# question_1.net
KiCad netlist of a schematic drawn in EAGLE
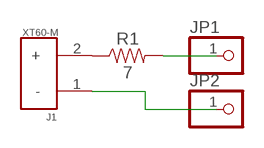
[diagram p0: schematic, sheet 1]

(export (version "E")
  (design (tool "Eeschema 10.0.6"))
  (components
    (comp (ref "J1")
      (value "XT60-M")
      (footprint "eagle-import:AMASS_XT60-M")
      (fields (field (name "MF") "AMASS"))
      (libsource (lib "eagle-import") (part "XT60-M"))
    )
    (comp (ref "JP1")
      (value "PINHD-1X1")
      (footprint "eagle-import:1X01")
      (libsource (lib "eagle-import") (part "PINHD-1X1"))
    )
    (comp (ref "JP2")
      (value "PINHD-1X1")
      (footprint "eagle-import:1X01")
      (libsource (lib "eagle-import") (part "PINHD-1X1"))
    )
    (comp (ref "R1")
      (value "7")
      (footprint "eagle-import:0603")
      (libsource (lib "eagle-import") (part "10OHM-0603-1/10W-1%"))
    )
  )
  (nets
    (net (code "1") (name "Net-(J1-+)") (class "Default")
      (node (ref "J1") (pin "2") (pinfunction "+_2") (pintype "passive"))
      (node (ref "R1") (pin "1") (pinfunction "1_1") (pintype "passive"))
    )
    (net (code "2") (name "Net-(J1--)") (class "Default")
      (node (ref "J1") (pin "1") (pinfunction "-_1") (pintype "passive"))
      (node (ref "JP2") (pin "1") (pinfunction "1_1") (pintype "passive"))
    )
    (net (code "3") (name "Net-(JP1-Pad1)") (class "Default")
      (node (ref "JP1") (pin "1") (pinfunction "1_1") (pintype "passive"))
      (node (ref "R1") (pin "2") (pinfunction "2_2") (pintype "passive"))
    )
  )
)
